# INVERTER_2.net
KiCad netlist of a schematic drawn in Altium Designer
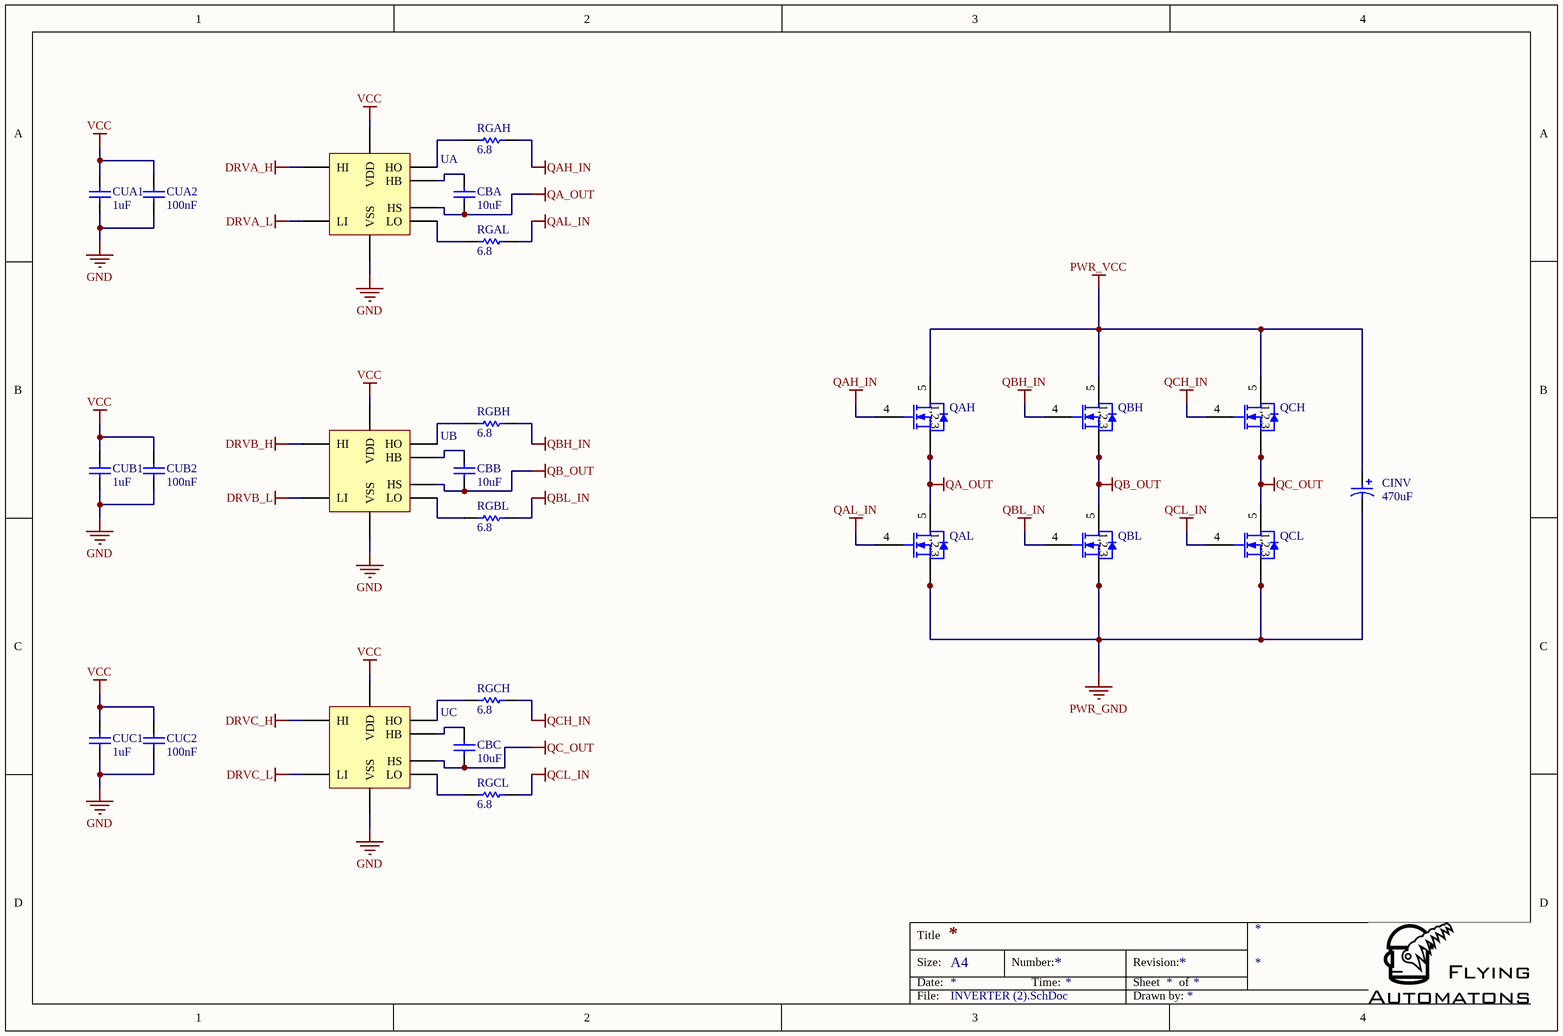
[diagram p0: INVERTER (2).SchDoc]

(export (version "E")
  (design (tool "Eeschema 10.0.6"))
  (components
    (comp (ref "CBA")
      (value "10uF")
      (footprint "CAPC3216L")
      (description "CAP CER 10UF 25V Y5V 1206")
      (fields (field (name "MANUFACTURER PART NUMBER") "TMK316F106ZL-T"))
      (libsource (lib "Passive#csv") (part "CAP_10u_1206_25V_Y5V"))
    )
    (comp (ref "CBB")
      (value "10uF")
      (footprint "CAPC3216L")
      (description "CAP CER 10UF 25V Y5V 1206")
      (fields (field (name "MANUFACTURER PART NUMBER") "TMK316F106ZL-T"))
      (libsource (lib "Passive#csv") (part "CAP_10u_1206_25V_Y5V"))
    )
    (comp (ref "CBC")
      (value "10uF")
      (footprint "CAPC3216L")
      (description "CAP CER 10UF 25V Y5V 1206")
      (fields (field (name "MANUFACTURER PART NUMBER") "TMK316F106ZL-T"))
      (libsource (lib "Passive#csv") (part "CAP_10u_1206_25V_Y5V"))
    )
    (comp (ref "CINV")
      (value "470uF")
      (footprint "CAP_RADIAL-CAN_SMD_M10")
      (description "CAP ALUM 470UF 25V 20% SMD")
      (fields
        (field (name "MANUFACTURER") "Nichicon")
        (field (name "MANUFACTURER PART NUMBER") "UCW1E471MNL1GS")
      )
      (libsource (lib "Passive#csv") (part "CAP_E_470u_Dia10_25V_Al_20%"))
    )
    (comp (ref "CUA1")
      (value "1uF")
      (footprint "CAPC1608L")
      (description "CAP CER 1UF 25V 10% X5R 0603")
      (fields (field (name "MANUFACTURER PART NUMBER") "TMK107BJ105KA-T"))
      (libsource (lib "Passive#csv") (part "CAP_1u_0603_25V_X5R_10%"))
    )
    (comp (ref "CUA2")
      (value "100nF")
      (footprint "CAPC1608L")
      (description "CAP CER 0.1UF 50V Y5V 0603")
      (fields (field (name "MANUFACTURER PART NUMBER") "CC0603ZRY5V9BB104"))
      (libsource (lib "Passive#csv") (part "CAP_100n_0603_50V_Y5V"))
    )
    (comp (ref "CUB1")
      (value "1uF")
      (footprint "CAPC1608L")
      (description "CAP CER 1UF 25V 10% X5R 0603")
      (fields (field (name "MANUFACTURER PART NUMBER") "TMK107BJ105KA-T"))
      (libsource (lib "Passive#csv") (part "CAP_1u_0603_25V_X5R_10%"))
    )
    (comp (ref "CUB2")
      (value "100nF")
      (footprint "CAPC1608L")
      (description "CAP CER 0.1UF 50V Y5V 0603")
      (fields (field (name "MANUFACTURER PART NUMBER") "CC0603ZRY5V9BB104"))
      (libsource (lib "Passive#csv") (part "CAP_100n_0603_50V_Y5V"))
    )
    (comp (ref "CUC1")
      (value "1uF")
      (footprint "CAPC1608L")
      (description "CAP CER 1UF 25V 10% X5R 0603")
      (fields (field (name "MANUFACTURER PART NUMBER") "TMK107BJ105KA-T"))
      (libsource (lib "Passive#csv") (part "CAP_1u_0603_25V_X5R_10%"))
    )
    (comp (ref "CUC2")
      (value "100nF")
      (footprint "CAPC1608L")
      (description "CAP CER 0.1UF 50V Y5V 0603")
      (fields (field (name "MANUFACTURER PART NUMBER") "CC0603ZRY5V9BB104"))
      (libsource (lib "Passive#csv") (part "CAP_100n_0603_50V_Y5V"))
    )
    (comp (ref "QAH")
      (value "~")
      (footprint "x-NXP_LFPAK33")
      (description "TRANSISTOR MOSFET N-CHANN 25V 8.6MOHM")
      (fields
        (field (name "MANUFACTURER") "NXP Semiconductors")
        (field (name "MANUFACTURER PART NUMBER") "PSMN9R0-25MLC,115")
      )
      (libsource (lib "Discrete#csv") (part "PSMN9R0-25MLC"))
    )
    (comp (ref "QAL")
      (value "~")
      (footprint "x-NXP_LFPAK33")
      (description "TRANSISTOR MOSFET N-CHANN 25V 8.6MOHM")
      (fields
        (field (name "MANUFACTURER") "NXP Semiconductors")
        (field (name "MANUFACTURER PART NUMBER") "PSMN9R0-25MLC,115")
      )
      (libsource (lib "Discrete#csv") (part "PSMN9R0-25MLC"))
    )
    (comp (ref "QBH")
      (value "~")
      (footprint "x-NXP_LFPAK33")
      (description "TRANSISTOR MOSFET N-CHANN 25V 8.6MOHM")
      (fields
        (field (name "MANUFACTURER") "NXP Semiconductors")
        (field (name "MANUFACTURER PART NUMBER") "PSMN9R0-25MLC,115")
      )
      (libsource (lib "Discrete#csv") (part "PSMN9R0-25MLC"))
    )
    (comp (ref "QBL")
      (value "~")
      (footprint "x-NXP_LFPAK33")
      (description "TRANSISTOR MOSFET N-CHANN 25V 8.6MOHM")
      (fields
        (field (name "MANUFACTURER") "NXP Semiconductors")
        (field (name "MANUFACTURER PART NUMBER") "PSMN9R0-25MLC,115")
      )
      (libsource (lib "Discrete#csv") (part "PSMN9R0-25MLC"))
    )
    (comp (ref "QCH")
      (value "~")
      (footprint "x-NXP_LFPAK33")
      (description "TRANSISTOR MOSFET N-CHANN 25V 8.6MOHM")
      (fields
        (field (name "MANUFACTURER") "NXP Semiconductors")
        (field (name "MANUFACTURER PART NUMBER") "PSMN9R0-25MLC,115")
      )
      (libsource (lib "Discrete#csv") (part "PSMN9R0-25MLC"))
    )
    (comp (ref "QCL")
      (value "~")
      (footprint "x-NXP_LFPAK33")
      (description "TRANSISTOR MOSFET N-CHANN 25V 8.6MOHM")
      (fields
        (field (name "MANUFACTURER") "NXP Semiconductors")
        (field (name "MANUFACTURER PART NUMBER") "PSMN9R0-25MLC,115")
      )
      (libsource (lib "Discrete#csv") (part "PSMN9R0-25MLC"))
    )
    (comp (ref "RGAH")
      (value "6.8")
      (footprint "RESC1608L")
      (description "RES 6.8 OHM 1/10W 1% 0603")
      (fields
        (field (name "MANUFACTURER") "Stackpole Electronics Inc")
        (field (name "MANUFACTURER PART NUMBER") "RMCF0603FT6R80")
      )
      (libsource (lib "Passive#csv") (part "RES_6R8_0603_0W1_1%"))
    )
    (comp (ref "RGAL")
      (value "6.8")
      (footprint "RESC1608L")
      (description "RES 6.8 OHM 1/10W 1% 0603")
      (fields
        (field (name "MANUFACTURER") "Stackpole Electronics Inc")
        (field (name "MANUFACTURER PART NUMBER") "RMCF0603FT6R80")
      )
      (libsource (lib "Passive#csv") (part "RES_6R8_0603_0W1_1%"))
    )
    (comp (ref "RGBH")
      (value "6.8")
      (footprint "RESC1608L")
      (description "RES 6.8 OHM 1/10W 1% 0603")
      (fields
        (field (name "MANUFACTURER") "Stackpole Electronics Inc")
        (field (name "MANUFACTURER PART NUMBER") "RMCF0603FT6R80")
      )
      (libsource (lib "Passive#csv") (part "RES_6R8_0603_0W1_1%"))
    )
    (comp (ref "RGBL")
      (value "6.8")
      (footprint "RESC1608L")
      (description "RES 6.8 OHM 1/10W 1% 0603")
      (fields
        (field (name "MANUFACTURER") "Stackpole Electronics Inc")
        (field (name "MANUFACTURER PART NUMBER") "RMCF0603FT6R80")
      )
      (libsource (lib "Passive#csv") (part "RES_6R8_0603_0W1_1%"))
    )
    (comp (ref "RGCH")
      (value "6.8")
      (footprint "RESC1608L")
      (description "RES 6.8 OHM 1/10W 1% 0603")
      (fields
        (field (name "MANUFACTURER") "Stackpole Electronics Inc")
        (field (name "MANUFACTURER PART NUMBER") "RMCF0603FT6R80")
      )
      (libsource (lib "Passive#csv") (part "RES_6R8_0603_0W1_1%"))
    )
    (comp (ref "RGCL")
      (value "6.8")
      (footprint "RESC1608L")
      (description "RES 6.8 OHM 1/10W 1% 0603")
      (fields
        (field (name "MANUFACTURER") "Stackpole Electronics Inc")
        (field (name "MANUFACTURER PART NUMBER") "RMCF0603FT6R80")
      )
      (libsource (lib "Passive#csv") (part "RES_6R8_0603_0W1_1%"))
    )
    (comp (ref "UA")
      (value "UCC27201A")
      (footprint "x-TI_S-PVSON-N9")
      (description "IC DVR HIGH/LOW SIDE 3A 9SON")
      (fields
        (field (name "MANUFACTURER") "Texas Instruments")
        (field (name "MANUFACTURER PART NUMBER") "UCC27201ADRCT")
      )
      (libsource (lib "Power_IC#csv") (part "x-TI_UCC27201A"))
    )
    (comp (ref "UB")
      (value "UCC27201A")
      (footprint "x-TI_S-PVSON-N9")
      (description "IC DVR HIGH/LOW SIDE 3A 9SON")
      (fields
        (field (name "MANUFACTURER") "Texas Instruments")
        (field (name "MANUFACTURER PART NUMBER") "UCC27201ADRCT")
      )
      (libsource (lib "Power_IC#csv") (part "x-TI_UCC27201A"))
    )
    (comp (ref "UC")
      (value "UCC27201A")
      (footprint "x-TI_S-PVSON-N9")
      (description "IC DVR HIGH/LOW SIDE 3A 9SON")
      (fields
        (field (name "MANUFACTURER") "Texas Instruments")
        (field (name "MANUFACTURER PART NUMBER") "UCC27201ADRCT")
      )
      (libsource (lib "Power_IC#csv") (part "x-TI_UCC27201A"))
    )
  )
  (nets
    (net (code "1") (name "DRVA_H") (class "Default")
      (node (ref "UA") (pin "6") (pinfunction "HI_6") (pintype "passive"))
    )
    (net (code "2") (name "DRVA_L") (class "Default")
      (node (ref "UA") (pin "7") (pinfunction "LI_7") (pintype "passive"))
    )
    (net (code "3") (name "DRVB_H") (class "Default")
      (node (ref "UB") (pin "6") (pinfunction "HI_6") (pintype "passive"))
    )
    (net (code "4") (name "DRVB_L") (class "Default")
      (node (ref "UB") (pin "7") (pinfunction "LI_7") (pintype "passive"))
    )
    (net (code "5") (name "DRVC_H") (class "Default")
      (node (ref "UC") (pin "6") (pinfunction "HI_6") (pintype "passive"))
    )
    (net (code "6") (name "DRVC_L") (class "Default")
      (node (ref "UC") (pin "7") (pinfunction "LI_7") (pintype "passive"))
    )
    (net (code "7") (name "GND") (class "Default")
      (node (ref "CUA1") (pin "2") (pinfunction "2_2") (pintype "passive"))
      (node (ref "CUA2") (pin "2") (pinfunction "2_2") (pintype "passive"))
      (node (ref "CUB1") (pin "2") (pinfunction "2_2") (pintype "passive"))
      (node (ref "CUB2") (pin "2") (pinfunction "2_2") (pintype "passive"))
      (node (ref "CUC1") (pin "2") (pinfunction "2_2") (pintype "passive"))
      (node (ref "CUC2") (pin "2") (pinfunction "2_2") (pintype "passive"))
      (node (ref "UA") (pin "8") (pinfunction "VSS_8") (pintype "passive"))
      (node (ref "UB") (pin "8") (pinfunction "VSS_8") (pintype "passive"))
      (node (ref "UC") (pin "8") (pinfunction "VSS_8") (pintype "passive"))
    )
    (net (code "8") (name "Net-(UA-HB)") (class "Default")
      (node (ref "CBA") (pin "1") (pinfunction "1_1") (pintype "passive"))
      (node (ref "UA") (pin "2") (pinfunction "HB_2") (pintype "passive"))
    )
    (net (code "9") (name "Net-(UA-HO)") (class "Default")
      (node (ref "RGAH") (pin "2") (pinfunction "2_2") (pintype "passive"))
      (node (ref "UA") (pin "3") (pinfunction "HO_3") (pintype "passive"))
    )
    (net (code "10") (name "Net-(UA-LO)") (class "Default")
      (node (ref "RGAL") (pin "2") (pinfunction "2_2") (pintype "passive"))
      (node (ref "UA") (pin "9") (pinfunction "LO_9") (pintype "passive"))
    )
    (net (code "11") (name "Net-(UB-HB)") (class "Default")
      (node (ref "CBB") (pin "1") (pinfunction "1_1") (pintype "passive"))
      (node (ref "UB") (pin "2") (pinfunction "HB_2") (pintype "passive"))
    )
    (net (code "12") (name "Net-(UB-HO)") (class "Default")
      (node (ref "RGBH") (pin "2") (pinfunction "2_2") (pintype "passive"))
      (node (ref "UB") (pin "3") (pinfunction "HO_3") (pintype "passive"))
    )
    (net (code "13") (name "Net-(UB-LO)") (class "Default")
      (node (ref "RGBL") (pin "2") (pinfunction "2_2") (pintype "passive"))
      (node (ref "UB") (pin "9") (pinfunction "LO_9") (pintype "passive"))
    )
    (net (code "14") (name "Net-(UC-HB)") (class "Default")
      (node (ref "CBC") (pin "1") (pinfunction "1_1") (pintype "passive"))
      (node (ref "UC") (pin "2") (pinfunction "HB_2") (pintype "passive"))
    )
    (net (code "15") (name "Net-(UC-HO)") (class "Default")
      (node (ref "RGCH") (pin "2") (pinfunction "2_2") (pintype "passive"))
      (node (ref "UC") (pin "3") (pinfunction "HO_3") (pintype "passive"))
    )
    (net (code "16") (name "Net-(UC-LO)") (class "Default")
      (node (ref "RGCL") (pin "2") (pinfunction "2_2") (pintype "passive"))
      (node (ref "UC") (pin "9") (pinfunction "LO_9") (pintype "passive"))
    )
    (net (code "17") (name "PWR_GND") (class "Default")
      (node (ref "CINV") (pin "2") (pinfunction "2_2") (pintype "passive"))
      (node (ref "QAL") (pin "1") (pinfunction "S_1") (pintype "passive"))
      (node (ref "QAL") (pin "2") (pinfunction "S_2") (pintype "passive"))
      (node (ref "QAL") (pin "3") (pinfunction "S_3") (pintype "passive"))
      (node (ref "QBL") (pin "1") (pinfunction "S_1") (pintype "passive"))
      (node (ref "QBL") (pin "2") (pinfunction "S_2") (pintype "passive"))
      (node (ref "QBL") (pin "3") (pinfunction "S_3") (pintype "passive"))
      (node (ref "QCL") (pin "1") (pinfunction "S_1") (pintype "passive"))
      (node (ref "QCL") (pin "2") (pinfunction "S_2") (pintype "passive"))
      (node (ref "QCL") (pin "3") (pinfunction "S_3") (pintype "passive"))
    )
    (net (code "18") (name "PWR_VCC") (class "Default")
      (node (ref "CINV") (pin "1") (pinfunction "1_1") (pintype "passive"))
      (node (ref "QAH") (pin "5") (pinfunction "D_5") (pintype "passive"))
      (node (ref "QBH") (pin "5") (pinfunction "D_5") (pintype "passive"))
      (node (ref "QCH") (pin "5") (pinfunction "D_5") (pintype "passive"))
    )
    (net (code "19") (name "QAH_IN") (class "Default")
      (node (ref "QAH") (pin "4") (pinfunction "G_4") (pintype "passive"))
      (node (ref "RGAH") (pin "1") (pinfunction "1_1") (pintype "passive"))
    )
    (net (code "20") (name "QAL_IN") (class "Default")
      (node (ref "QAL") (pin "4") (pinfunction "G_4") (pintype "passive"))
      (node (ref "RGAL") (pin "1") (pinfunction "1_1") (pintype "passive"))
    )
    (net (code "21") (name "QA_OUT") (class "Default")
      (node (ref "CBA") (pin "2") (pinfunction "2_2") (pintype "passive"))
      (node (ref "QAH") (pin "1") (pinfunction "S_1") (pintype "passive"))
      (node (ref "QAH") (pin "2") (pinfunction "S_2") (pintype "passive"))
      (node (ref "QAH") (pin "3") (pinfunction "S_3") (pintype "passive"))
      (node (ref "QAL") (pin "5") (pinfunction "D_5") (pintype "passive"))
      (node (ref "UA") (pin "4") (pinfunction "HS_4") (pintype "passive"))
    )
    (net (code "22") (name "QBH_IN") (class "Default")
      (node (ref "QBH") (pin "4") (pinfunction "G_4") (pintype "passive"))
      (node (ref "RGBH") (pin "1") (pinfunction "1_1") (pintype "passive"))
    )
    (net (code "23") (name "QBL_IN") (class "Default")
      (node (ref "QBL") (pin "4") (pinfunction "G_4") (pintype "passive"))
      (node (ref "RGBL") (pin "1") (pinfunction "1_1") (pintype "passive"))
    )
    (net (code "24") (name "QB_OUT") (class "Default")
      (node (ref "CBB") (pin "2") (pinfunction "2_2") (pintype "passive"))
      (node (ref "QBH") (pin "1") (pinfunction "S_1") (pintype "passive"))
      (node (ref "QBH") (pin "2") (pinfunction "S_2") (pintype "passive"))
      (node (ref "QBH") (pin "3") (pinfunction "S_3") (pintype "passive"))
      (node (ref "QBL") (pin "5") (pinfunction "D_5") (pintype "passive"))
      (node (ref "UB") (pin "4") (pinfunction "HS_4") (pintype "passive"))
    )
    (net (code "25") (name "QCH_IN") (class "Default")
      (node (ref "QCH") (pin "4") (pinfunction "G_4") (pintype "passive"))
      (node (ref "RGCH") (pin "1") (pinfunction "1_1") (pintype "passive"))
    )
    (net (code "26") (name "QCL_IN") (class "Default")
      (node (ref "QCL") (pin "4") (pinfunction "G_4") (pintype "passive"))
      (node (ref "RGCL") (pin "1") (pinfunction "1_1") (pintype "passive"))
    )
    (net (code "27") (name "QC_OUT") (class "Default")
      (node (ref "CBC") (pin "2") (pinfunction "2_2") (pintype "passive"))
      (node (ref "QCH") (pin "1") (pinfunction "S_1") (pintype "passive"))
      (node (ref "QCH") (pin "2") (pinfunction "S_2") (pintype "passive"))
      (node (ref "QCH") (pin "3") (pinfunction "S_3") (pintype "passive"))
      (node (ref "QCL") (pin "5") (pinfunction "D_5") (pintype "passive"))
      (node (ref "UC") (pin "4") (pinfunction "HS_4") (pintype "passive"))
    )
    (net (code "28") (name "VCC") (class "Default")
      (node (ref "CUA1") (pin "1") (pinfunction "1_1") (pintype "passive"))
      (node (ref "CUA2") (pin "1") (pinfunction "1_1") (pintype "passive"))
      (node (ref "CUB1") (pin "1") (pinfunction "1_1") (pintype "passive"))
      (node (ref "CUB2") (pin "1") (pinfunction "1_1") (pintype "passive"))
      (node (ref "CUC1") (pin "1") (pinfunction "1_1") (pintype "passive"))
      (node (ref "CUC2") (pin "1") (pinfunction "1_1") (pintype "passive"))
      (node (ref "UA") (pin "1") (pinfunction "VDD_1") (pintype "passive"))
      (node (ref "UB") (pin "1") (pinfunction "VDD_1") (pintype "passive"))
      (node (ref "UC") (pin "1") (pinfunction "VDD_1") (pintype "passive"))
    )
  )
)
